# TSMP-Resistors.net
KiCad netlist of a schematic drawn in Altium Designer
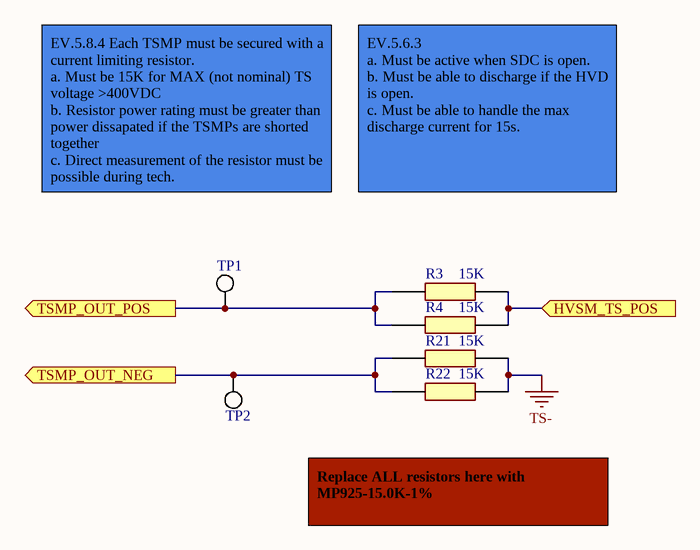
[diagram p0: TSMP-Resistors.SchDoc]

(export (version "E")
  (design (tool "Eeschema 10.0.6"))
  (components
    (comp (ref "R3")
      (value "15K")
      (footprint "TO508P344X1041X2058-2P")
      (description "Thick Film Resistors - Through Hole 15K ohm 25W 1% TO-220 PKG PWR FILM")
      (fields
        (field (name "MOUSER PART NUMBER") "684-MP925-15K")
        (field (name "MANUFACTURER_PART_NUMBER") "MP925-15.0K-1%")
      )
      (libsource (lib "SchLib1") (part "MP925-15.0K-1%"))
    )
    (comp (ref "R4")
      (value "15K")
      (footprint "TO508P344X1041X2058-2P")
      (description "Thick Film Resistors - Through Hole 15K ohm 25W 1% TO-220 PKG PWR FILM")
      (fields
        (field (name "MOUSER PART NUMBER") "684-MP925-15K")
        (field (name "MANUFACTURER_PART_NUMBER") "MP925-15.0K-1%")
      )
      (libsource (lib "SchLib1") (part "MP925-15.0K-1%"))
    )
    (comp (ref "R21")
      (value "15K")
      (footprint "TO508P344X1041X2058-2P")
      (description "Thick Film Resistors - Through Hole 15K ohm 25W 1% TO-220 PKG PWR FILM")
      (fields
        (field (name "MOUSER PART NUMBER") "684-MP925-15K")
        (field (name "MANUFACTURER_PART_NUMBER") "MP925-15.0K-1%")
      )
      (libsource (lib "SchLib1") (part "MP925-15.0K-1%"))
    )
    (comp (ref "R22")
      (value "15K")
      (footprint "TO508P344X1041X2058-2P")
      (description "Thick Film Resistors - Through Hole 15K ohm 25W 1% TO-220 PKG PWR FILM")
      (fields
        (field (name "MOUSER PART NUMBER") "684-MP925-15K")
        (field (name "MANUFACTURER_PART_NUMBER") "MP925-15.0K-1%")
      )
      (libsource (lib "SchLib1") (part "MP925-15.0K-1%"))
    )
    (comp (ref "TP1")
      (value "~")
      (footprint "FOOTPRINT-GENERIC-TP-VIA-1MM")
      (libsource (lib "University of California Riverside - FSAE") (part "Misc-Generic-TP"))
    )
    (comp (ref "TP2")
      (value "~")
      (footprint "FOOTPRINT-GENERIC-TP-VIA-1MM")
      (libsource (lib "University of California Riverside - FSAE") (part "Misc-Generic-TP"))
    )
  )
  (nets
    (net (code "1") (name "/HVSM_TS_POS") (class "Default")
      (node (ref "R3") (pin "2") (pinfunction "2_2") (pintype "passive"))
      (node (ref "R4") (pin "2") (pinfunction "2_2") (pintype "passive"))
    )
    (net (code "2") (name "/TSMP_OUT_NEG") (class "Default")
      (node (ref "R21") (pin "1") (pinfunction "1_1") (pintype "passive"))
      (node (ref "R22") (pin "1") (pinfunction "1_1") (pintype "passive"))
      (node (ref "TP2") (pin "1") (pinfunction "TP_1") (pintype "passive"))
    )
    (net (code "3") (name "/TSMP_OUT_POS") (class "Default")
      (node (ref "R3") (pin "1") (pinfunction "1_1") (pintype "passive"))
      (node (ref "R4") (pin "1") (pinfunction "1_1") (pintype "passive"))
      (node (ref "TP1") (pin "1") (pinfunction "TP_1") (pintype "passive"))
    )
    (net (code "4") (name "TS-") (class "Default")
      (node (ref "R21") (pin "2") (pinfunction "2_2") (pintype "passive"))
      (node (ref "R22") (pin "2") (pinfunction "2_2") (pintype "passive"))
    )
  )
)
